# IntrusionNode_v2.net
KiCad netlist of a schematic drawn in EAGLE
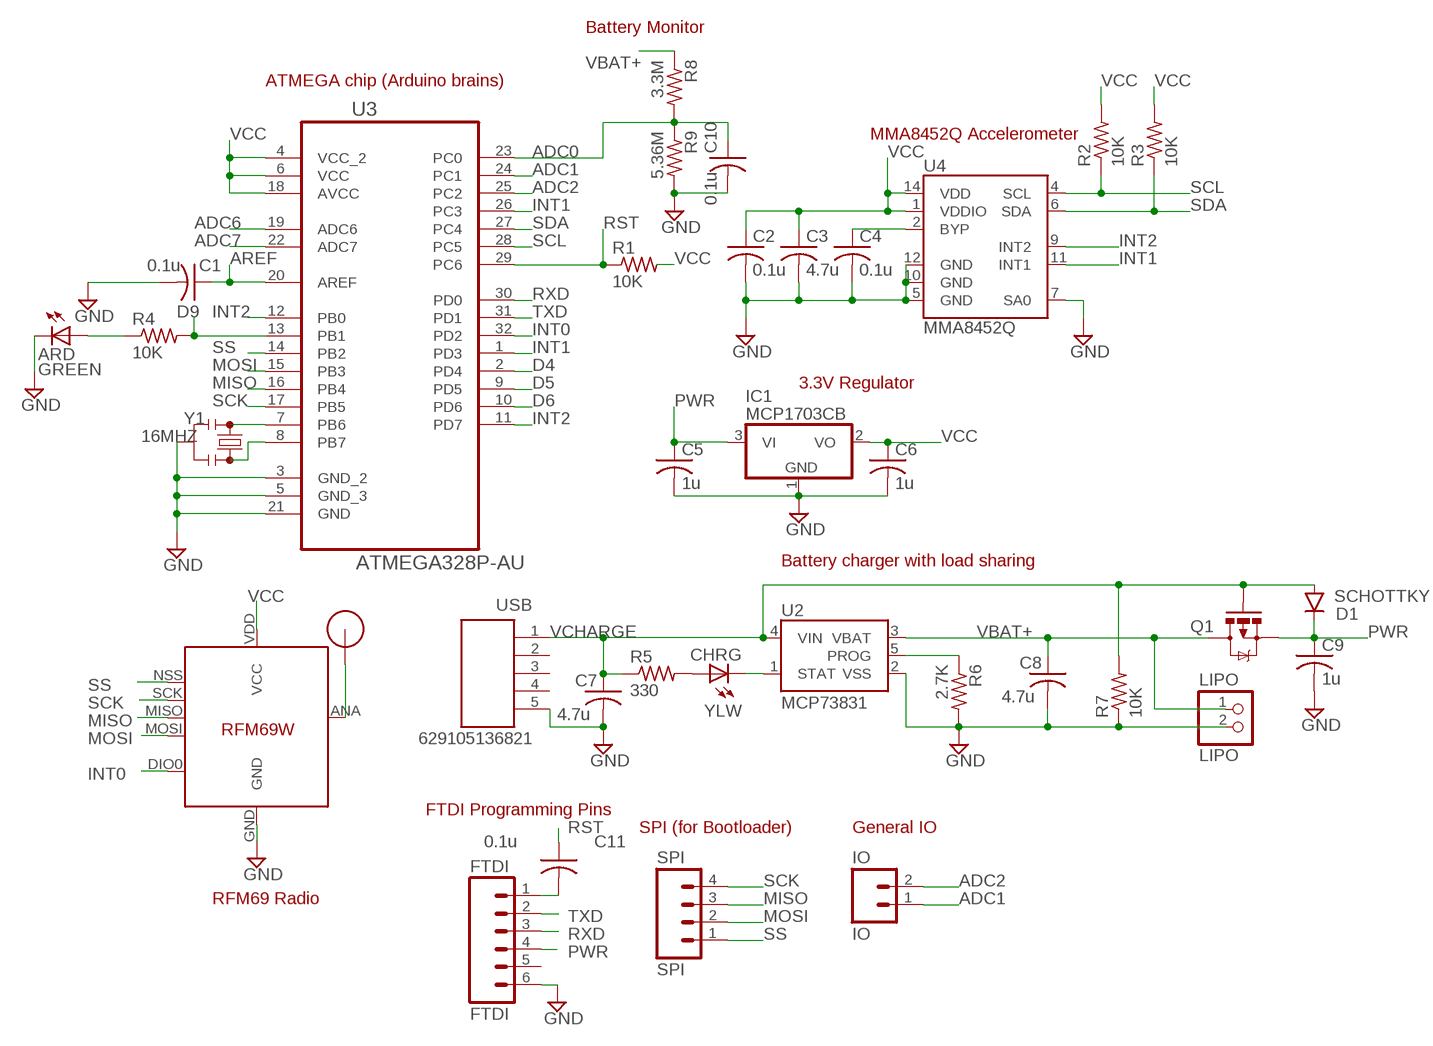
[diagram p0: schematic, sheet 1]

(export (version "E")
  (design (tool "Eeschema 10.0.6"))
  (components
    (comp (ref "ANT")
      (value "RFM12B_ANTENNA")
      (footprint "eagle-import:RFM12B-ANTENNA")
      (libsource (lib "eagle-import") (part "RFM12B_ANTENNA"))
    )
    (comp (ref "ARD")
      (value "GREEN")
      (footprint "eagle-import:CHIPLED_0805")
      (fields (field (name "PARTNO") "LG R971-KN-1"))
      (libsource (lib "eagle-import") (part "LEDCHIPLED_0805"))
    )
    (comp (ref "C1")
      (value "0.1u")
      (footprint "eagle-import:C0805")
      (fields (field (name "PARTNO") "CL21B104KBCNNNC"))
      (libsource (lib "eagle-import") (part "C-USC0805"))
    )
    (comp (ref "C2")
      (value "0.1u")
      (footprint "eagle-import:C0805")
      (fields (field (name "PARTNO") "CL21B104KBCNNNC"))
      (libsource (lib "eagle-import") (part "C-USC0805"))
    )
    (comp (ref "C3")
      (value "4.7u")
      (footprint "eagle-import:C0805")
      (fields (field (name "PARTNO") "CL21A475KPFNNNE"))
      (libsource (lib "eagle-import") (part "C-USC0805"))
    )
    (comp (ref "C4")
      (value "0.1u")
      (footprint "eagle-import:C0805")
      (fields (field (name "PARTNO") "CL21B104KBCNNNC"))
      (libsource (lib "eagle-import") (part "C-USC0805"))
    )
    (comp (ref "C5")
      (value "1u")
      (footprint "eagle-import:C0805")
      (fields (field (name "PARTNO") "CL21B105KPFNNNE"))
      (libsource (lib "eagle-import") (part "C-USC0805"))
    )
    (comp (ref "C6")
      (value "1u")
      (footprint "eagle-import:C0805")
      (fields (field (name "PARTNO") "CL21B105KPFNNNE"))
      (libsource (lib "eagle-import") (part "C-USC0805"))
    )
    (comp (ref "C7")
      (value "4.7u")
      (footprint "eagle-import:C0805")
      (fields (field (name "PARTNO") "CL21A475KPFNNNE"))
      (libsource (lib "eagle-import") (part "C-USC0805"))
    )
    (comp (ref "C8")
      (value "4.7u")
      (footprint "eagle-import:C0805")
      (fields (field (name "PARTNO") "CL21A475KPFNNNE"))
      (libsource (lib "eagle-import") (part "C-USC0805"))
    )
    (comp (ref "C9")
      (value "1u")
      (footprint "eagle-import:C0805")
      (fields (field (name "PARTNO") "CL21B105KPFNNNE"))
      (libsource (lib "eagle-import") (part "C-USC0805"))
    )
    (comp (ref "C10")
      (value "0.1u")
      (footprint "eagle-import:C0805")
      (fields (field (name "PARTNO") "CL21B104KBCNNNC"))
      (libsource (lib "eagle-import") (part "C-USC0805"))
    )
    (comp (ref "C11")
      (value "0.1u")
      (footprint "eagle-import:C0805")
      (fields (field (name "PARTNO") "CL21B104KBCNNNC"))
      (libsource (lib "eagle-import") (part "C-USC0805"))
    )
    (comp (ref "CHRG")
      (value "YLW")
      (footprint "eagle-import:CHIPLED_0805")
      (fields (field (name "PARTNO") "LY R976-PS-36"))
      (libsource (lib "eagle-import") (part "LEDCHIPLED_0805"))
    )
    (comp (ref "D1")
      (value "SCHOTTKY")
      (footprint "eagle-import:SOD-123")
      (fields (field (name "PARTNO") "B130LAW-7-F"))
      (libsource (lib "eagle-import") (part "DIODESOD123"))
    )
    (comp (ref "FTDI")
      (value "FTDI")
      (footprint "eagle-import:1X06_LOCK_LONGPADS")
      (fields (field (name "PARTNO") "PEC36SAAN"))
      (libsource (lib "eagle-import") (part "M06LOCK_LONGPADS"))
    )
    (comp (ref "IC1")
      (value "MCP1703CB")
      (footprint "eagle-import:SOT23")
      (fields (field (name "PARTNO") "MCP1703T-3302E/CB"))
      (libsource (lib "eagle-import") (part "MCP1703CB"))
    )
    (comp (ref "IO")
      (value "IO")
      (footprint "eagle-import:1X02_LOCK_LONGPADS")
      (libsource (lib "eagle-import") (part "M02LOCK_LONGPADS"))
    )
    (comp (ref "LIPO")
      (value "LIPO")
      (footprint "eagle-import:JST-PH-2-SMT-RA")
      (fields (field (name "PARTNO") "S2B-PH-SM4-TB(LF)(SN)"))
      (libsource (lib "eagle-import") (part "JST_2PIN-SMT-RA"))
    )
    (comp (ref "Q1")
      (value "MOSFET-PCHANNELSMD")
      (footprint "eagle-import:SOT23-3")
      (fields (field (name "PARTNO") "SSM3J328R,LF"))
      (libsource (lib "eagle-import") (part "MOSFET-PCHANNELSMD"))
    )
    (comp (ref "R1")
      (value "10K")
      (footprint "eagle-import:R0805")
      (fields (field (name "PARTNO") "RC2012J103CS"))
      (libsource (lib "eagle-import") (part "R-US_R0805"))
    )
    (comp (ref "R2")
      (value "10K")
      (footprint "eagle-import:R0805")
      (fields (field (name "PARTNO") "RC2012J103CS"))
      (libsource (lib "eagle-import") (part "R-US_R0805"))
    )
    (comp (ref "R3")
      (value "10K")
      (footprint "eagle-import:R0805")
      (fields (field (name "PARTNO") "RC2012J103CS"))
      (libsource (lib "eagle-import") (part "R-US_R0805"))
    )
    (comp (ref "R4")
      (value "10K")
      (footprint "eagle-import:R0805")
      (fields (field (name "PARTNO") "RC2012J103CS"))
      (libsource (lib "eagle-import") (part "R-US_R0805"))
    )
    (comp (ref "R5")
      (value "330")
      (footprint "eagle-import:R0805")
      (fields (field (name "PARTNO") "RC2012J331CS"))
      (libsource (lib "eagle-import") (part "R-US_R0805"))
    )
    (comp (ref "R6")
      (value "2.7K")
      (footprint "eagle-import:R0805")
      (fields (field (name "PARTNO") "RC2012J272CS"))
      (libsource (lib "eagle-import") (part "R-US_R0805"))
    )
    (comp (ref "R7")
      (value "10K")
      (footprint "eagle-import:R0805")
      (fields (field (name "PARTNO") "RC2012J103CS"))
      (libsource (lib "eagle-import") (part "R-US_R0805"))
    )
    (comp (ref "R8")
      (value "3.3M")
      (footprint "eagle-import:R0805")
      (fields (field (name "PARTNO") "RC2012F335CS"))
      (libsource (lib "eagle-import") (part "R-US_R0805"))
    )
    (comp (ref "R9")
      (value "5.36M")
      (footprint "eagle-import:R0805")
      (fields (field (name "PARTNO") "RC2012F5364CS"))
      (libsource (lib "eagle-import") (part "R-US_R0805"))
    )
    (comp (ref "SPI")
      (value "SPI")
      (footprint "eagle-import:1X04_LOCK_LONGPADS")
      (fields (field (name "PARTNO") "PEC36SAAN"))
      (libsource (lib "eagle-import") (part "M04LOCK_LONGPADS"))
    )
    (comp (ref "U1")
      (value "RFM69")
      (footprint "eagle-import:RFM69W-MINPADS")
      (fields (field (name "PARTNO") "RFM69W"))
      (libsource (lib "eagle-import") (part "RFM69"))
    )
    (comp (ref "U2")
      (value "MCP73831")
      (footprint "eagle-import:SOT23-5")
      (fields (field (name "PARTNO") "MCP73831T-2ATI/OT"))
      (libsource (lib "eagle-import") (part "MCP73831"))
    )
    (comp (ref "U3")
      (value "ATMEGA328P-AU")
      (footprint "eagle-import:QFP80P900X900X120-32N")
      (fields (field (name "PARTNO") "ATMEGA328P-AUR"))
      (libsource (lib "eagle-import") (part "ATMEGA328P-AU"))
    )
    (comp (ref "U4")
      (value "MMA8452Q")
      (footprint "eagle-import:QFN-16_0.5MM")
      (fields (field (name "PARTNO") "MMA8452QT"))
      (libsource (lib "eagle-import") (part "MMA8452Q"))
    )
    (comp (ref "USB")
      (value "629105136821")
      (footprint "eagle-import:629105136821")
      (libsource (lib "eagle-import") (part "629105136821"))
    )
    (comp (ref "Y1")
      (value "16MHZ")
      (footprint "eagle-import:RESONATOR-SMD")
      (fields (field (name "PARTNO") "CSTCE16M0V53-R0"))
      (libsource (lib "eagle-import") (part "RESONATOR16MHZ"))
    )
  )
  (nets
    (net (code "1") (name "/ADC0") (class "Default")
      (node (ref "C10") (pin "1") (pinfunction "1_1") (pintype "passive"))
      (node (ref "R8") (pin "2") (pinfunction "2_2") (pintype "passive"))
      (node (ref "R9") (pin "1") (pinfunction "1_1") (pintype "passive"))
      (node (ref "U3") (pin "23") (pinfunction "PC0_23") (pintype "bidirectional"))
    )
    (net (code "2") (name "/ADC1") (class "Default")
      (node (ref "IO") (pin "1") (pinfunction "1_1") (pintype "passive"))
      (node (ref "U3") (pin "24") (pinfunction "PC1_24") (pintype "bidirectional"))
    )
    (net (code "3") (name "/ADC2") (class "Default")
      (node (ref "IO") (pin "2") (pinfunction "2_2") (pintype "passive"))
      (node (ref "U3") (pin "25") (pinfunction "PC2_25") (pintype "bidirectional"))
    )
    (net (code "4") (name "/ADC6") (class "Default")
      (node (ref "U3") (pin "19") (pinfunction "ADC6_19") (pintype "input"))
    )
    (net (code "5") (name "/ADC7") (class "Default")
      (node (ref "U3") (pin "22") (pinfunction "ADC7_22") (pintype "input"))
    )
    (net (code "6") (name "/AREF") (class "Default")
      (node (ref "C1") (pin "1") (pinfunction "1_1") (pintype "passive"))
      (node (ref "U3") (pin "20") (pinfunction "AREF_20") (pintype "input"))
    )
    (net (code "7") (name "/D4") (class "Default")
      (node (ref "U3") (pin "2") (pinfunction "PD4_2") (pintype "bidirectional"))
    )
    (net (code "8") (name "/D5") (class "Default")
      (node (ref "U3") (pin "9") (pinfunction "PD5_9") (pintype "bidirectional"))
    )
    (net (code "9") (name "/D6") (class "Default")
      (node (ref "U3") (pin "10") (pinfunction "PD6_10") (pintype "bidirectional"))
    )
    (net (code "10") (name "/D9") (class "Default")
      (node (ref "R4") (pin "2") (pinfunction "2_2") (pintype "passive"))
      (node (ref "U3") (pin "13") (pinfunction "PB1_13") (pintype "bidirectional"))
    )
    (net (code "11") (name "/INT0") (class "Default")
      (node (ref "U1") (pin "DIO0") (pinfunction "DIO0_DIO0") (pintype "open_collector"))
      (node (ref "U3") (pin "32") (pinfunction "PD2_32") (pintype "bidirectional"))
    )
    (net (code "12") (name "/INT1") (class "Default")
      (node (ref "U3") (pin "1") (pinfunction "PD3_1") (pintype "bidirectional"))
      (node (ref "U3") (pin "26") (pinfunction "PC3_26") (pintype "bidirectional"))
      (node (ref "U4") (pin "11") (pinfunction "INT1_11") (pintype "bidirectional"))
    )
    (net (code "13") (name "/INT2") (class "Default")
      (node (ref "U3") (pin "11") (pinfunction "PD7_11") (pintype "bidirectional"))
      (node (ref "U3") (pin "12") (pinfunction "PB0_12") (pintype "bidirectional"))
      (node (ref "U4") (pin "9") (pinfunction "INT2_9") (pintype "bidirectional"))
    )
    (net (code "14") (name "/MISO") (class "Default")
      (node (ref "SPI") (pin "3") (pinfunction "3_3") (pintype "passive"))
      (node (ref "U1") (pin "MISO") (pinfunction "MISO_MISO") (pintype "input"))
      (node (ref "U3") (pin "16") (pinfunction "PB4_16") (pintype "bidirectional"))
    )
    (net (code "15") (name "/MOSI") (class "Default")
      (node (ref "SPI") (pin "2") (pinfunction "2_2") (pintype "passive"))
      (node (ref "U1") (pin "MOSI") (pinfunction "MOSI_MOSI") (pintype "output"))
      (node (ref "U3") (pin "15") (pinfunction "PB3_15") (pintype "bidirectional"))
    )
    (net (code "16") (name "/PWR") (class "Default")
      (node (ref "C5") (pin "1") (pinfunction "1_1") (pintype "passive"))
      (node (ref "C9") (pin "1") (pinfunction "1_1") (pintype "passive"))
      (node (ref "D1") (pin "C") (pinfunction "C_C") (pintype "passive"))
      (node (ref "FTDI") (pin "4") (pinfunction "4_4") (pintype "passive"))
      (node (ref "IC1") (pin "3") (pinfunction "VI_3") (pintype "input"))
      (node (ref "Q1") (pin "2") (pinfunction "S_2") (pintype "passive"))
    )
    (net (code "17") (name "/RST") (class "Default")
      (node (ref "C11") (pin "1") (pinfunction "1_1") (pintype "passive"))
      (node (ref "R1") (pin "1") (pinfunction "1_1") (pintype "passive"))
      (node (ref "U3") (pin "29") (pinfunction "PC6_29") (pintype "bidirectional"))
    )
    (net (code "18") (name "/RXD") (class "Default")
      (node (ref "FTDI") (pin "3") (pinfunction "3_3") (pintype "passive"))
      (node (ref "U3") (pin "30") (pinfunction "PD0_30") (pintype "bidirectional"))
    )
    (net (code "19") (name "/SCK") (class "Default")
      (node (ref "SPI") (pin "4") (pinfunction "4_4") (pintype "passive"))
      (node (ref "U1") (pin "SCK") (pinfunction "SCK_SCK") (pintype "input"))
      (node (ref "U3") (pin "17") (pinfunction "PB5_17") (pintype "bidirectional"))
    )
    (net (code "20") (name "/SCL") (class "Default")
      (node (ref "R2") (pin "1") (pinfunction "1_1") (pintype "passive"))
      (node (ref "U3") (pin "28") (pinfunction "PC5_28") (pintype "bidirectional"))
      (node (ref "U4") (pin "4") (pinfunction "SCL_4") (pintype "bidirectional"))
    )
    (net (code "21") (name "/SDA") (class "Default")
      (node (ref "R3") (pin "1") (pinfunction "1_1") (pintype "passive"))
      (node (ref "U3") (pin "27") (pinfunction "PC4_27") (pintype "bidirectional"))
      (node (ref "U4") (pin "6") (pinfunction "SDA_6") (pintype "bidirectional"))
    )
    (net (code "22") (name "/SS") (class "Default")
      (node (ref "SPI") (pin "1") (pinfunction "1_1") (pintype "passive"))
      (node (ref "U1") (pin "NSS") (pinfunction "SEL_NSS") (pintype "input"))
      (node (ref "U3") (pin "14") (pinfunction "PB2_14") (pintype "bidirectional"))
    )
    (net (code "23") (name "/TXD") (class "Default")
      (node (ref "FTDI") (pin "2") (pinfunction "2_2") (pintype "passive"))
      (node (ref "U3") (pin "31") (pinfunction "PD1_31") (pintype "bidirectional"))
    )
    (net (code "24") (name "/VBAT+") (class "Default")
      (node (ref "C8") (pin "1") (pinfunction "1_1") (pintype "passive"))
      (node (ref "LIPO") (pin "1") (pinfunction "2_1") (pintype "passive"))
      (node (ref "Q1") (pin "3") (pinfunction "D_3") (pintype "passive"))
      (node (ref "R8") (pin "1") (pinfunction "1_1") (pintype "passive"))
      (node (ref "U2") (pin "3") (pinfunction "VBAT_3") (pintype "power_in"))
    )
    (net (code "25") (name "/VCC") (class "Default")
      (node (ref "C2") (pin "1") (pinfunction "1_1") (pintype "passive"))
      (node (ref "C3") (pin "1") (pinfunction "1_1") (pintype "passive"))
      (node (ref "C6") (pin "1") (pinfunction "1_1") (pintype "passive"))
      (node (ref "IC1") (pin "2") (pinfunction "VO_2") (pintype "passive"))
      (node (ref "R1") (pin "2") (pinfunction "2_2") (pintype "passive"))
      (node (ref "R2") (pin "2") (pinfunction "2_2") (pintype "passive"))
      (node (ref "R3") (pin "2") (pinfunction "2_2") (pintype "passive"))
      (node (ref "U1") (pin "VDD") (pinfunction "VCC_VDD") (pintype "power_in"))
      (node (ref "U3") (pin "18") (pinfunction "AVCC_18") (pintype "power_in"))
      (node (ref "U3") (pin "4") (pinfunction "VCC_2_4") (pintype "power_in"))
      (node (ref "U3") (pin "6") (pinfunction "VCC_6") (pintype "power_in"))
      (node (ref "U4") (pin "1") (pinfunction "VDDIO_1") (pintype "bidirectional"))
      (node (ref "U4") (pin "14") (pinfunction "VDD_14") (pintype "bidirectional"))
    )
    (net (code "26") (name "/VCHARGE") (class "Default")
      (node (ref "C7") (pin "1") (pinfunction "1_1") (pintype "passive"))
      (node (ref "D1") (pin "A") (pinfunction "A_A") (pintype "passive"))
      (node (ref "Q1") (pin "1") (pinfunction "G_1") (pintype "passive"))
      (node (ref "R5") (pin "1") (pinfunction "1_1") (pintype "passive"))
      (node (ref "R7") (pin "2") (pinfunction "2_2") (pintype "passive"))
      (node (ref "U2") (pin "4") (pinfunction "VIN_4") (pintype "power_in"))
      (node (ref "USB") (pin "1") (pinfunction "1_1") (pintype "passive"))
    )
    (net (code "27") (name "GND") (class "Default")
      (node (ref "ARD") (pin "C") (pinfunction "C_C") (pintype "passive"))
      (node (ref "C1") (pin "2") (pinfunction "2_2") (pintype "passive"))
      (node (ref "C10") (pin "2") (pinfunction "2_2") (pintype "passive"))
      (node (ref "C2") (pin "2") (pinfunction "2_2") (pintype "passive"))
      (node (ref "C3") (pin "2") (pinfunction "2_2") (pintype "passive"))
      (node (ref "C4") (pin "2") (pinfunction "2_2") (pintype "passive"))
      (node (ref "C5") (pin "2") (pinfunction "2_2") (pintype "passive"))
      (node (ref "C6") (pin "2") (pinfunction "2_2") (pintype "passive"))
      (node (ref "C7") (pin "2") (pinfunction "2_2") (pintype "passive"))
      (node (ref "C8") (pin "2") (pinfunction "2_2") (pintype "passive"))
      (node (ref "C9") (pin "2") (pinfunction "2_2") (pintype "passive"))
      (node (ref "FTDI") (pin "6") (pinfunction "6_6") (pintype "passive"))
      (node (ref "IC1") (pin "1") (pinfunction "GND_1") (pintype "passive"))
      (node (ref "LIPO") (pin "2") (pinfunction "1_2") (pintype "passive"))
      (node (ref "R6") (pin "2") (pinfunction "2_2") (pintype "passive"))
      (node (ref "R7") (pin "1") (pinfunction "1_1") (pintype "passive"))
      (node (ref "R9") (pin "2") (pinfunction "2_2") (pintype "passive"))
      (node (ref "U1") (pin "GND") (pinfunction "GND_GND") (pintype "power_in"))
      (node (ref "U2") (pin "2") (pinfunction "VSS_2") (pintype "power_in"))
      (node (ref "U3") (pin "21") (pinfunction "GND_21") (pintype "passive"))
      (node (ref "U3") (pin "3") (pinfunction "GND_2_3") (pintype "passive"))
      (node (ref "U3") (pin "5") (pinfunction "GND_3_5") (pintype "passive"))
      (node (ref "U4") (pin "10") (pinfunction "GND_10") (pintype "bidirectional"))
      (node (ref "U4") (pin "12") (pinfunction "GND_12") (pintype "bidirectional"))
      (node (ref "U4") (pin "5") (pinfunction "GND_5") (pintype "bidirectional"))
      (node (ref "U4") (pin "7") (pinfunction "SA0_7") (pintype "bidirectional"))
      (node (ref "USB") (pin "5") (pinfunction "5_5") (pintype "passive"))
      (node (ref "Y1") (pin "2") (pinfunction "2_2") (pintype "passive"))
    )
    (net (code "28") (name "Net-(ANT-1)") (class "Default")
      (node (ref "ANT") (pin "P$1") (pinfunction "1_P$1") (pintype "bidirectional"))
      (node (ref "U1") (pin "ANA") (pinfunction "ANT_ANA") (pintype "passive"))
    )
    (net (code "29") (name "Net-(ARD-PadA)") (class "Default")
      (node (ref "ARD") (pin "A") (pinfunction "A_A") (pintype "passive"))
      (node (ref "R4") (pin "1") (pinfunction "1_1") (pintype "passive"))
    )
    (net (code "30") (name "Net-(C11-Pad2)") (class "Default")
      (node (ref "C11") (pin "2") (pinfunction "2_2") (pintype "passive"))
      (node (ref "FTDI") (pin "1") (pinfunction "1_1") (pintype "passive"))
    )
    (net (code "31") (name "Net-(CHRG-PadA)") (class "Default")
      (node (ref "CHRG") (pin "A") (pinfunction "A_A") (pintype "passive"))
      (node (ref "R5") (pin "2") (pinfunction "2_2") (pintype "passive"))
    )
    (net (code "32") (name "Net-(U2-PROG)") (class "Default")
      (node (ref "R6") (pin "1") (pinfunction "1_1") (pintype "passive"))
      (node (ref "U2") (pin "5") (pinfunction "PROG_5") (pintype "input"))
    )
    (net (code "33") (name "Net-(U2-STAT)") (class "Default")
      (node (ref "CHRG") (pin "C") (pinfunction "C_C") (pintype "passive"))
      (node (ref "U2") (pin "1") (pinfunction "STAT_1") (pintype "output"))
    )
    (net (code "34") (name "Net-(U3-PB6)") (class "Default")
      (node (ref "U3") (pin "7") (pinfunction "PB6_7") (pintype "bidirectional"))
      (node (ref "Y1") (pin "1") (pinfunction "1_1") (pintype "passive"))
    )
    (net (code "35") (name "Net-(U3-PB7)") (class "Default")
      (node (ref "U3") (pin "8") (pinfunction "PB7_8") (pintype "bidirectional"))
      (node (ref "Y1") (pin "3") (pinfunction "3_3") (pintype "passive"))
    )
    (net (code "36") (name "Net-(U4-BYP)") (class "Default")
      (node (ref "C4") (pin "1") (pinfunction "1_1") (pintype "passive"))
      (node (ref "U4") (pin "2") (pinfunction "BYP_2") (pintype "bidirectional"))
    )
    (net (code "37") (name "unconnected-(FTDI-Pad5)") (class "Default")
      (node (ref "FTDI") (pin "5") (pinfunction "5_5") (pintype "passive"))
    )
    (net (code "38") (name "unconnected-(USB-Pad2)") (class "Default")
      (node (ref "USB") (pin "2") (pinfunction "2_2") (pintype "passive"))
    )
    (net (code "39") (name "unconnected-(USB-Pad3)") (class "Default")
      (node (ref "USB") (pin "3") (pinfunction "3_3") (pintype "passive"))
    )
    (net (code "40") (name "unconnected-(USB-Pad4)") (class "Default")
      (node (ref "USB") (pin "4") (pinfunction "4_4") (pintype "passive"))
    )
  )
)
